# AudioAmplifier.net
KiCad netlist of a schematic drawn in Altium Designer
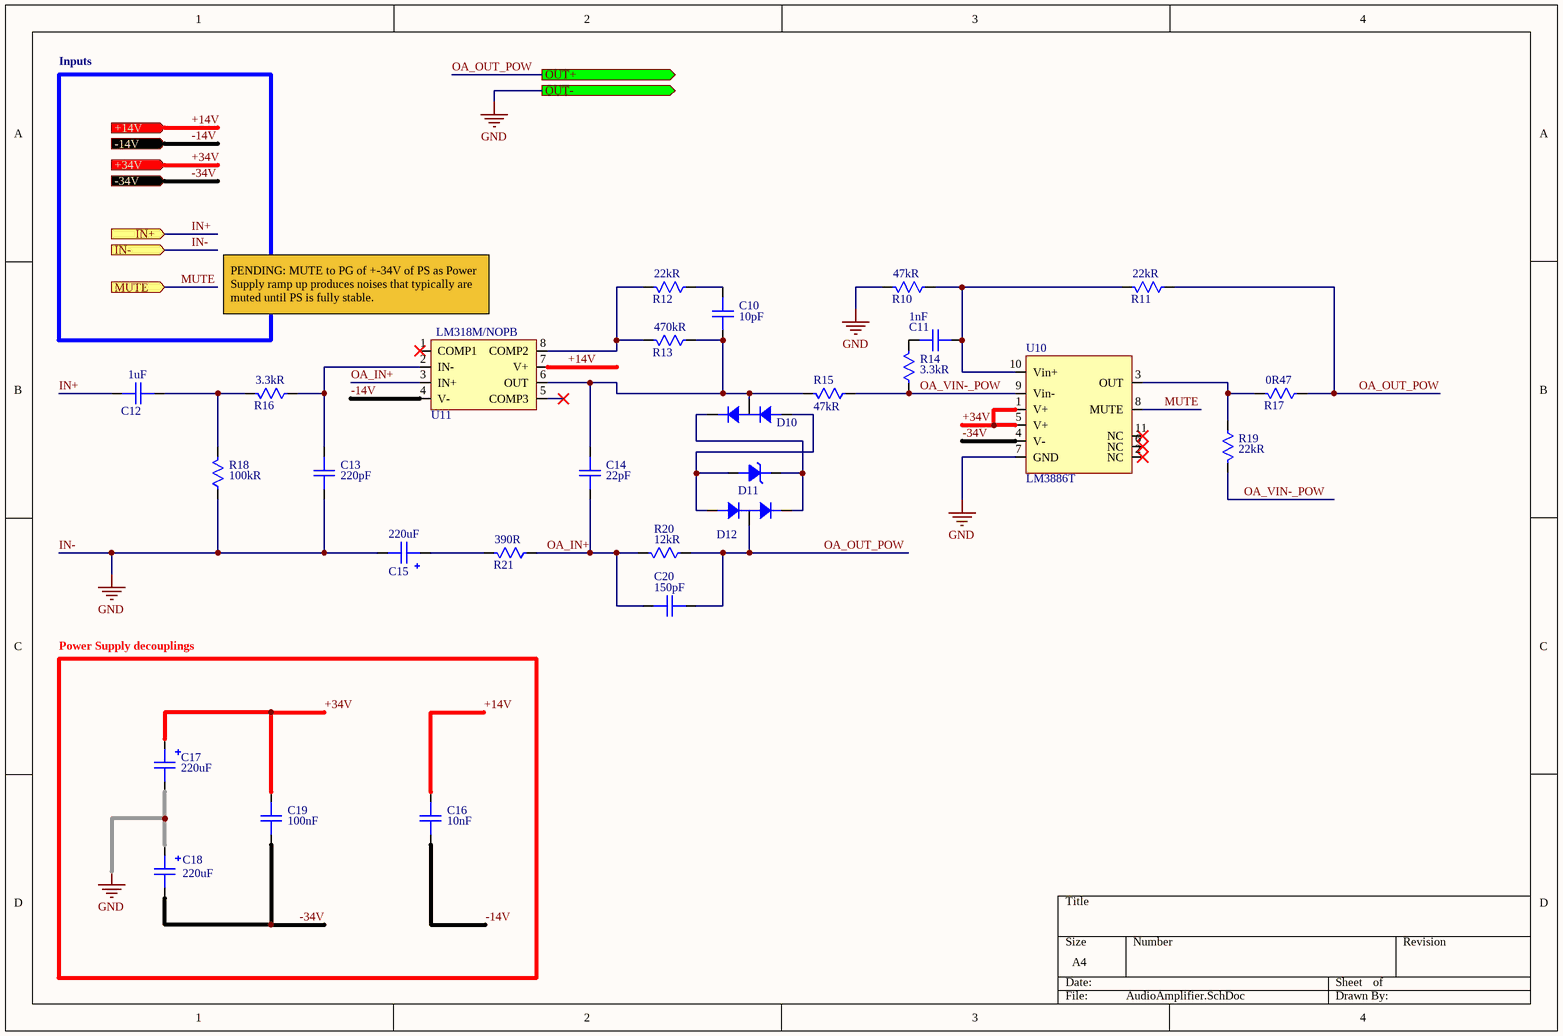
[diagram p0: AudioAmplifier.SchDoc]

(export (version "E")
  (design (tool "Eeschema 10.0.6"))
  (components
    (comp (ref "C10")
      (value "GRM21A5C2D100JW01D")
      (footprint "CAPC2012X10N-GRM0805-MURATA")
      (description "Cap Ceramic 10pF 200V C0G 5% Pad SMD 0805 125C T/R")
      (fields
        (field (name "MANUFACTURER") "Murata")
        (field (name "CAPACITANCE") "10pF")
        (field (name "TOLERANCE") "5%")
      )
      (libsource (lib "AudioAmpSchLib") (part "GRM21A5C2D100JW01D"))
    )
    (comp (ref "C11")
      (value "GRM219R72A102KA01D")
      (footprint "CAPC2012X10N-GRM0805-MURATA")
      (description "0805 1 nF 100 V ±10 % Tolerance X7R Surface Mount Multilayer Ceramic Capacitor")
      (fields
        (field (name "MANUFACTURER") "Murata")
        (field (name "CAPACITANCE") "1nF")
        (field (name "TOLERANCE") "10%")
      )
      (libsource (lib "AudioAmpSchLib") (part "GRM219R72A102KA01D"))
    )
    (comp (ref "C12")
      (value "SMDTC04100VA00KR00")
      (footprint "Chip2PinSM127P600-8N-4030-SMD-PET-WIMA")
      (description "Cap Film 1UF 10% 63VDC 4030")
      (fields
        (field (name "MANUFACTURER") "WIMA")
        (field (name "CAPACITANCE") "1uF")
        (field (name "TOLERANCE") "10%")
      )
      (libsource (lib "AudioAmpSchLib") (part "SMDTC04100VA00KR00"))
    )
    (comp (ref "C13")
      (value "GRM219R72A221KA01D")
      (footprint "CAPC2012X10N-GRM0805-MURATA")
      (description "Cap Ceramic 220pF 100V X7R 10% SMD 0805 125°C Paper T/R")
      (fields
        (field (name "MANUFACTURER") "Murata")
        (field (name "CAPACITANCE") "220pF")
        (field (name "TOLERANCE") "10%")
      )
      (libsource (lib "AudioAmpSchLib") (part "GRM219R72A221KA01D"))
    )
    (comp (ref "C14")
      (value "GRM21A5C2D220JW01D")
      (footprint "CAPC2012X10N-GRM0805-MURATA")
      (description "Cap Ceramic 22pF 200V C0G 5% SMD 0805 125°C Paper T/R")
      (fields
        (field (name "MANUFACTURER") "Murata")
        (field (name "CAPACITANCE") "22pF")
        (field (name "TOLERANCE") "5%")
      )
      (libsource (lib "AudioAmpSchLib") (part "GRM21A5C2D220JW01D"))
    )
    (comp (ref "C15")
      (value "ESH227M063AH4AA")
      (footprint "Capacitor-KEMET-H4")
      (description "Cap, 220ΜF, 63V, 20%")
      (fields
        (field (name "MANUFACTURER") "KEMET")
        (field (name "CAPACITANCE") "220uF")
        (field (name "TOLERANCE") "20%")
      )
      (libsource (lib "AudioAmpSchLib") (part "ESH227M063AH4AA"))
    )
    (comp (ref "C16")
      (value "GRM219R72A103KA01D")
      (footprint "CAPC2012X10N-GRM0805-MURATA")
      (description "Cap Ceramic 0.01uF 100V X7R 10% SMD 0805 125°C Paper T/R")
      (fields
        (field (name "MANUFACTURER") "Murata")
        (field (name "TOLERANCE") "10%")
        (field (name "CAPACITANCE") "10nF")
      )
      (libsource (lib "AudioAmpSchLib") (part "GRM219R72A103KA01D"))
    )
    (comp (ref "C17")
      (value "ESH227M063AH4AA")
      (footprint "Capacitor-KEMET-H4")
      (description "Cap, 220ΜF, 63V, 20%")
      (fields
        (field (name "MANUFACTURER") "KEMET")
        (field (name "CAPACITANCE") "220uF")
        (field (name "TOLERANCE") "20%")
      )
      (libsource (lib "AudioAmpSchLib") (part "ESH227M063AH4AA"))
    )
    (comp (ref "C18")
      (value "ESH227M063AH4AA")
      (footprint "Capacitor-KEMET-H4")
      (description "Cap, 220ΜF, 63V, 20%")
      (fields
        (field (name "MANUFACTURER") "KEMET")
        (field (name "CAPACITANCE") "220uF")
        (field (name "TOLERANCE") "20%")
      )
      (libsource (lib "AudioAmpSchLib") (part "ESH227M063AH4AA"))
    )
    (comp (ref "C19")
      (value "GRM21BR72A104KAC4L")
      (footprint "CAPC2012X10N-GRM0805-MURATA")
      (description "0805 0.1 uF 100 V ±10% Tolerance X7R SMT Multilayer Ceramic Capacitor")
      (fields
        (field (name "MANUFACTURER") "Murata")
        (field (name "CAPACITANCE") "100nF")
        (field (name "TOLERANCE") "10%")
      )
      (libsource (lib "AudioAmpSchLib") (part "GRM21BR72A104KAC4L"))
    )
    (comp (ref "C20")
      (value "GRM2165C2A151JA01D")
      (footprint "CAPC2012X10N-GRM0805-MURATA")
      (description "Cap Ceramic 150pF 100V C0G 5% SMD 0805 125°C Paper T/R")
      (fields
        (field (name "MANUFACTURER") "Murata")
        (field (name "CAPACITANCE") "150pF")
        (field (name "TOLERANCE") "5%")
      )
      (libsource (lib "AudioAmpSchLib") (part "GRM2165C2A151JA01D"))
    )
    (comp (ref "D10")
      (value "BAV99W,LF")
      (footprint "SOT65P210X100-3N-SOT-323-TOSHIBA")
      (description "Switching Diode Series 0.9pF 100V 3-Pin SOT-323")
      (fields (field (name "MANUFACTURER") "Toshiba"))
      (libsource (lib "AudioAmpSchLib") (part "BAV99W,LF"))
    )
    (comp (ref "D11")
      (value "BZV55-C27,115")
      (footprint "DIOMELF3515N-SOD80C-NEXPERIA")
      (description "Zener diode BZV55C27 Hottech; SMD; MiniMELF, LL-34 (SOD-80); 27V; 0, 5W; 5%")
      (fields (field (name "MANUFACTURER") "Nexperia"))
      (libsource (lib "AudioAmpSchLib") (part "BZV55-C27,115"))
    )
    (comp (ref "D12")
      (value "BAV99W,LF")
      (footprint "SOT65P210X100-3N-SOT-323-TOSHIBA")
      (description "Switching Diode Series 0.9pF 100V 3-Pin SOT-323")
      (fields (field (name "MANUFACTURER") "Toshiba"))
      (libsource (lib "AudioAmpSchLib") (part "BAV99W,LF"))
    )
    (comp (ref "R10")
      (value "RK73H2BTTD4702F")
      (footprint "Chip2PinSM127P600-8N-RK73H-1206-KOA")
      (description "Res Thick Film 1206 47K Ohm 1% 0.25W(1/4W) ±100ppm/C Pad SMD Automotive T/R")
      (fields
        (field (name "MANUFACTURER") "KOA Speer")
        (field (name "RESISTANCE") "47kR")
        (field (name "TOLERANCE") "1%")
      )
      (libsource (lib "AudioAmpSchLib") (part "RK73H2BTTD4702F"))
    )
    (comp (ref "R11")
      (value "RK73B2BTTDD223J")
      (footprint "Chip2PinSM127P600-8N-RK73H-1206-KOA")
      (description "Thick Film Resistors 1/4W 22K OHM 5%")
      (fields
        (field (name "MANUFACTURER") "KOA Speer")
        (field (name "TOLERANCE") "5%")
        (field (name "RESISTANCE") "22kR")
      )
      (libsource (lib "AudioAmpSchLib") (part "RK73B2BTTDD223J"))
    )
    (comp (ref "R12")
      (value "RK73B2BTTDD223J")
      (footprint "Chip2PinSM127P600-8N-RK73H-1206-KOA")
      (description "Thick Film Resistors 1/4W 22K OHM 5%")
      (fields
        (field (name "MANUFACTURER") "KOA Speer")
        (field (name "TOLERANCE") "5%")
        (field (name "RESISTANCE") "22kR")
      )
      (libsource (lib "AudioAmpSchLib") (part "RK73B2BTTDD223J"))
    )
    (comp (ref "R13")
      (value "SG732BTTD474K")
      (footprint "Chip2PinSM127P600-8N-RK73H-1206-KOA")
      (description "anti-surge thick film chip resistor, 1206, RoHS")
      (fields
        (field (name "MANUFACTURER") "KOA Speer")
        (field (name "RESISTANCE") "470kR")
        (field (name "TOLERANCE") "10%")
      )
      (libsource (lib "AudioAmpSchLib") (part "SG732BTTD474K"))
    )
    (comp (ref "R14")
      (value "RK73B2BTTDD332J")
      (footprint "Chip2PinSM127P600-8N-RK73H-1206-KOA")
      (description "Thick Film Resistors 3.3K OHM 5%")
      (fields
        (field (name "MANUFACTURER") "KOA Speer")
        (field (name "RESISTANCE") "3.3kR")
        (field (name "TOLERANCE") "5%")
      )
      (libsource (lib "AudioAmpSchLib") (part "RK73B2BTTDD332J"))
    )
    (comp (ref "R15")
      (value "RK73H2BTTD4702F")
      (footprint "Chip2PinSM127P600-8N-RK73H-1206-KOA")
      (description "Res Thick Film 1206 47K Ohm 1% 0.25W(1/4W) ±100ppm/C Pad SMD Automotive T/R")
      (fields
        (field (name "MANUFACTURER") "KOA Speer")
        (field (name "RESISTANCE") "47kR")
        (field (name "TOLERANCE") "1%")
      )
      (libsource (lib "AudioAmpSchLib") (part "RK73H2BTTD4702F"))
    )
    (comp (ref "R16")
      (value "RK73B2BTTDD332J")
      (footprint "Chip2PinSM127P600-8N-RK73H-1206-KOA")
      (description "Thick Film Resistors 3.3K OHM 5%")
      (fields
        (field (name "MANUFACTURER") "KOA Speer")
        (field (name "RESISTANCE") "3.3kR")
        (field (name "TOLERANCE") "5%")
      )
      (libsource (lib "AudioAmpSchLib") (part "RK73B2BTTDD332J"))
    )
    (comp (ref "R17")
      (value "RWS7 R47 J T&R")
      (footprint "Chip2PinSM127P600-8N-RWS7-OHMITE")
      (description "7 Watts Wirewound SMD 470 Milliohms 5% Tape Reel / ARCOL")
      (fields (field (name "MANUFACTURER") "Ohmite") (field (name "RESISTANCE") "0R47"))
      (libsource (lib "AudioAmpSchLib") (part "RWS7 R47 J T&R"))
    )
    (comp (ref "R18")
      (value "RK73B2BTTDD104J")
      (footprint "Chip2PinSM127P600-8N-RK73H-1206-KOA")
      (description "Thick Film Resistors - SMD 1/4watts 100Kohms 5%")
      (fields
        (field (name "MANUFACTURER") "KOA Speer")
        (field (name "RESISTANCE") "100kR")
        (field (name "TOLERANCE") "5%")
      )
      (libsource (lib "AudioAmpSchLib") (part "RK73B2BTTDD104J"))
    )
    (comp (ref "R19")
      (value "RK73B2BTTDD223J")
      (footprint "Chip2PinSM127P600-8N-RK73H-1206-KOA")
      (description "Thick Film Resistors 1/4W 22K OHM 5%")
      (fields
        (field (name "MANUFACTURER") "KOA Speer")
        (field (name "TOLERANCE") "5%")
        (field (name "RESISTANCE") "22kR")
      )
      (libsource (lib "AudioAmpSchLib") (part "RK73B2BTTDD223J"))
    )
    (comp (ref "R20")
      (value "RK73H2BTTD1202F")
      (footprint "Chip2PinSM127P600-8N-RK73H-1206-KOA")
      (description "Res Thick Film 1206 12K Ohm 1% 0.25W(1/4W) ±100ppm/C Pad SMD Automotive T/R")
      (fields
        (field (name "MANUFACTURER") "KOA Speer")
        (field (name "RESISTANCE") "12kR")
        (field (name "TOLERANCE") "1%")
      )
      (libsource (lib "AudioAmpSchLib") (part "RK73H2BTTD1202F"))
    )
    (comp (ref "R21")
      (value "RK73B2BTTDD391J")
      (footprint "Chip2PinSM127P600-8N-RK73H-1206-KOA")
      (description "Thick Film Resistors - SMD 1/4W 390 OHM 5%")
      (fields
        (field (name "MANUFACTURER") "KOA Speer")
        (field (name "RESISTANCE") "390R")
        (field (name "TOLERANCE") "5%")
      )
      (libsource (lib "AudioAmpSchLib") (part "RK73B2BTTDD391J"))
    )
    (comp (ref "U10")
      (value "LM3886T")
      (footprint "TF11B")
      (description "Audio Amp Speaker 1-CH Mono 68W Class-AB 11-Pin(11+Tab) TO-220 Rail")
      (fields (field (name "MANUFACTURER") "TI National Semiconductor"))
      (libsource (lib "AudioAmpSchLib") (part "LM3886T"))
    )
    (comp (ref "U11")
      (value "LM318M/NOPB")
      (footprint "SOIC127P600X175-8N-SOIC8-D0008A-TI")
      (description "LM318-N Single 40V, 15MHZ, High")
      (fields
        (field (name "MANUFACTURER") "TI National Semiconductor")
        (field (name "MANUFACTURER PART NUMBER") "LM318M/NOPB")
      )
      (libsource (lib "AudioAmpSchLib") (part "LM318M/NOPB"))
    )
  )
  (nets
    (net (code "1") (name "/+14V") (class "Default")
      (node (ref "C16") (pin "2") (pinfunction "2_2") (pintype "passive"))
      (node (ref "U11") (pin "7") (pinfunction "V+_7") (pintype "passive"))
    )
    (net (code "2") (name "/+34V") (class "Default")
      (node (ref "C17") (pin "1") (pinfunction "1_1") (pintype "passive"))
      (node (ref "C19") (pin "2") (pinfunction "2_2") (pintype "passive"))
      (node (ref "U10") (pin "1") (pinfunction "V+_1") (pintype "passive"))
      (node (ref "U10") (pin "5") (pinfunction "V+_5") (pintype "passive"))
    )
    (net (code "3") (name "/-14V") (class "Default")
      (node (ref "C16") (pin "1") (pinfunction "1_1") (pintype "passive"))
      (node (ref "U11") (pin "4") (pinfunction "V-_4") (pintype "passive"))
    )
    (net (code "4") (name "/-34V") (class "Default")
      (node (ref "C18") (pin "2") (pinfunction "2_2") (pintype "passive"))
      (node (ref "C19") (pin "1") (pinfunction "1_1") (pintype "passive"))
      (node (ref "U10") (pin "4") (pinfunction "V-_4") (pintype "passive"))
    )
    (net (code "5") (name "/IN+") (class "Default")
      (node (ref "C12") (pin "2") (pinfunction "2_2") (pintype "passive"))
    )
    (net (code "6") (name "/MUTE") (class "Default")
      (node (ref "U10") (pin "8") (pinfunction "MUTE_8") (pintype "passive"))
    )
    (net (code "7") (name "/OA_IN+") (class "Default")
      (node (ref "C14") (pin "2") (pinfunction "2_2") (pintype "passive"))
      (node (ref "C20") (pin "2") (pinfunction "2_2") (pintype "passive"))
      (node (ref "R20") (pin "1") (pinfunction "1_1") (pintype "passive"))
      (node (ref "R21") (pin "2") (pinfunction "2_2") (pintype "passive"))
      (node (ref "U11") (pin "3") (pinfunction "IN+_3") (pintype "passive"))
    )
    (net (code "8") (name "/OA_OUT_POW") (class "Default")
      (node (ref "C20") (pin "1") (pinfunction "1_1") (pintype "passive"))
      (node (ref "D12") (pin "K1A2") (pinfunction "K1A2_K1A2") (pintype "passive"))
      (node (ref "R11") (pin "2") (pinfunction "2_2") (pintype "passive"))
      (node (ref "R17") (pin "2") (pinfunction "2_2") (pintype "passive"))
      (node (ref "R20") (pin "2") (pinfunction "2_2") (pintype "passive"))
    )
    (net (code "9") (name "/OA_VIN-_POW") (class "Default")
      (node (ref "R14") (pin "2") (pinfunction "2_2") (pintype "passive"))
      (node (ref "R15") (pin "2") (pinfunction "2_2") (pintype "passive"))
      (node (ref "R19") (pin "1") (pinfunction "1_1") (pintype "passive"))
      (node (ref "U10") (pin "9") (pinfunction "Vin-_9") (pintype "passive"))
    )
    (net (code "10") (name "GND") (class "Default")
      (node (ref "C13") (pin "1") (pinfunction "1_1") (pintype "passive"))
      (node (ref "C15") (pin "2") (pinfunction "2_2") (pintype "passive"))
      (node (ref "C17") (pin "2") (pinfunction "2_2") (pintype "passive"))
      (node (ref "C18") (pin "1") (pinfunction "1_1") (pintype "passive"))
      (node (ref "R10") (pin "1") (pinfunction "1_1") (pintype "passive"))
      (node (ref "R18") (pin "2") (pinfunction "2_2") (pintype "passive"))
      (node (ref "U10") (pin "7") (pinfunction "GND_7") (pintype "passive"))
    )
    (net (code "11") (name "Net-(C10-Pad2)") (class "Default")
      (node (ref "C10") (pin "2") (pinfunction "2_2") (pintype "passive"))
      (node (ref "R12") (pin "2") (pinfunction "2_2") (pintype "passive"))
    )
    (net (code "12") (name "Net-(C11-Pad2)") (class "Default")
      (node (ref "C11") (pin "2") (pinfunction "2_2") (pintype "passive"))
      (node (ref "R14") (pin "1") (pinfunction "1_1") (pintype "passive"))
    )
    (net (code "13") (name "Net-(C12-Pad1)") (class "Default")
      (node (ref "C12") (pin "1") (pinfunction "1_1") (pintype "passive"))
      (node (ref "R16") (pin "1") (pinfunction "1_1") (pintype "passive"))
      (node (ref "R18") (pin "1") (pinfunction "1_1") (pintype "passive"))
    )
    (net (code "14") (name "Net-(C15-Pad1)") (class "Default")
      (node (ref "C15") (pin "1") (pinfunction "1_1") (pintype "passive"))
      (node (ref "R21") (pin "1") (pinfunction "1_1") (pintype "passive"))
    )
    (net (code "15") (name "Net-(D10-PadA1)") (class "Default")
      (node (ref "D10") (pin "A1") (pinfunction "A1_A1") (pintype "passive"))
      (node (ref "D11") (pin "A") (pinfunction "A_A") (pintype "passive"))
      (node (ref "D12") (pin "A1") (pinfunction "A1_A1") (pintype "passive"))
    )
    (net (code "16") (name "Net-(D10-PadK2)") (class "Default")
      (node (ref "D10") (pin "K2") (pinfunction "K2_K2") (pintype "passive"))
      (node (ref "D11") (pin "K") (pinfunction "K_K") (pintype "passive"))
      (node (ref "D12") (pin "K2") (pinfunction "K2_K2") (pintype "passive"))
    )
    (net (code "17") (name "Net-(U10-OUT)") (class "Default")
      (node (ref "R17") (pin "1") (pinfunction "1_1") (pintype "passive"))
      (node (ref "R19") (pin "2") (pinfunction "2_2") (pintype "passive"))
      (node (ref "U10") (pin "3") (pinfunction "OUT_3") (pintype "passive"))
    )
    (net (code "18") (name "Net-(U10-Vin+)") (class "Default")
      (node (ref "C11") (pin "1") (pinfunction "1_1") (pintype "passive"))
      (node (ref "R10") (pin "2") (pinfunction "2_2") (pintype "passive"))
      (node (ref "R11") (pin "1") (pinfunction "1_1") (pintype "passive"))
      (node (ref "U10") (pin "10") (pinfunction "Vin+_10") (pintype "passive"))
    )
    (net (code "19") (name "Net-(U11-COMP2)") (class "Default")
      (node (ref "R12") (pin "1") (pinfunction "1_1") (pintype "passive"))
      (node (ref "R13") (pin "1") (pinfunction "1_1") (pintype "passive"))
      (node (ref "U11") (pin "8") (pinfunction "COMP2_8") (pintype "passive"))
    )
    (net (code "20") (name "Net-(U11-IN-)") (class "Default")
      (node (ref "C13") (pin "2") (pinfunction "2_2") (pintype "passive"))
      (node (ref "R16") (pin "2") (pinfunction "2_2") (pintype "passive"))
      (node (ref "U11") (pin "2") (pinfunction "IN-_2") (pintype "passive"))
    )
    (net (code "21") (name "Net-(U11-OUT)") (class "Default")
      (node (ref "C10") (pin "1") (pinfunction "1_1") (pintype "passive"))
      (node (ref "C14") (pin "1") (pinfunction "1_1") (pintype "passive"))
      (node (ref "D10") (pin "K1A2") (pinfunction "K1A2_K1A2") (pintype "passive"))
      (node (ref "R13") (pin "2") (pinfunction "2_2") (pintype "passive"))
      (node (ref "R15") (pin "1") (pinfunction "1_1") (pintype "passive"))
      (node (ref "U11") (pin "6") (pinfunction "OUT_6") (pintype "passive"))
    )
    (net (code "22") (name "unconnected-(U10-NC-Pad2)") (class "Default")
      (node (ref "U10") (pin "2") (pinfunction "NC_2") (pintype "passive+no_connect"))
    )
    (net (code "23") (name "unconnected-(U10-NC-Pad6)") (class "Default")
      (node (ref "U10") (pin "6") (pinfunction "NC_6") (pintype "passive+no_connect"))
    )
    (net (code "24") (name "unconnected-(U10-NC-Pad11)") (class "Default")
      (node (ref "U10") (pin "11") (pinfunction "NC_11") (pintype "passive+no_connect"))
    )
    (net (code "25") (name "unconnected-(U11-COMP1-Pad1)") (class "Default")
      (node (ref "U11") (pin "1") (pinfunction "COMP1_1") (pintype "passive+no_connect"))
    )
    (net (code "26") (name "unconnected-(U11-COMP3-Pad5)") (class "Default")
      (node (ref "U11") (pin "5") (pinfunction "COMP3_5") (pintype "passive+no_connect"))
    )
  )
)
